# BPS_PowerSupply_v1-0.net
KiCad netlist of a schematic drawn in Altium Designer
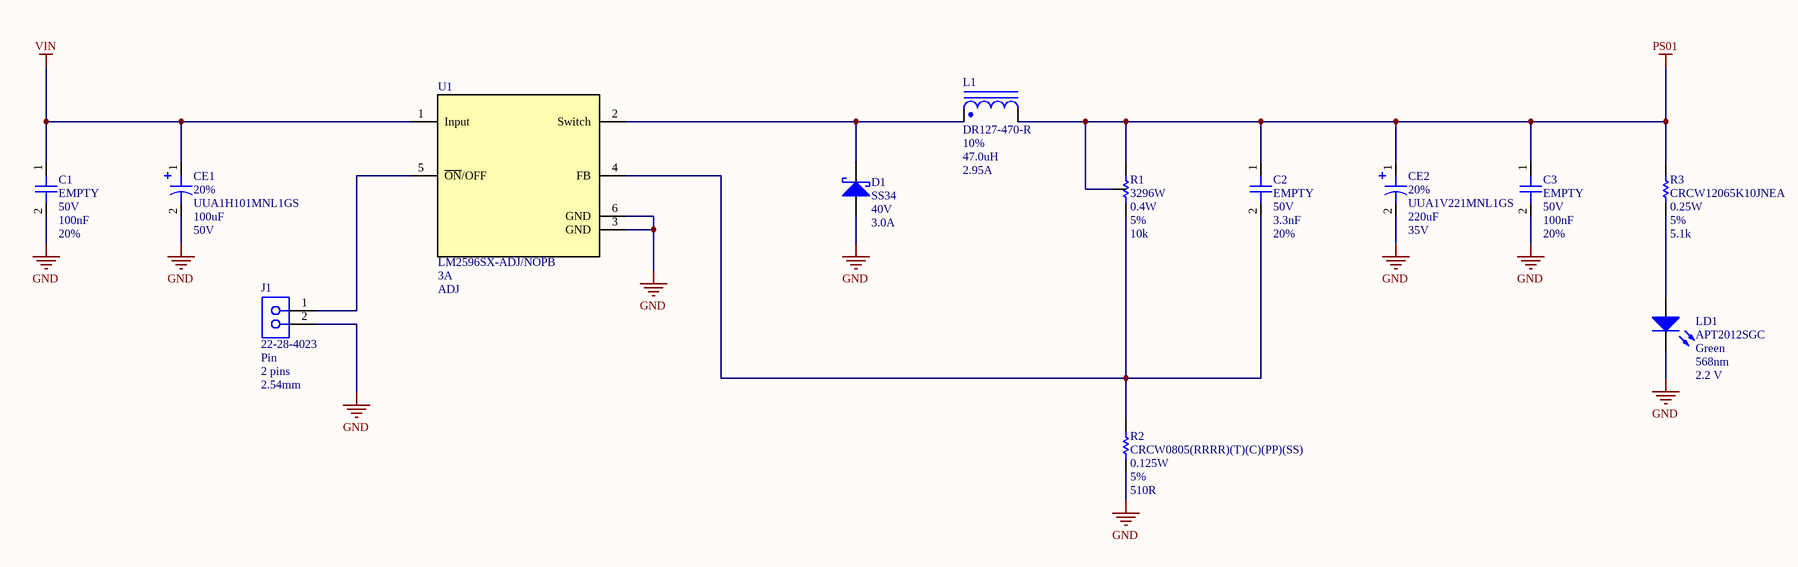
[diagram p0: BPS_PowerSupply_v1-0.SchDoc]

(export (version "E")
  (design (tool "Eeschema 10.0.6"))
  (components
    (comp (ref "C1")
      (value "100nF")
      (footprint "Cap0805")
      (description "Surface Mount Multilayer Ceramic Chip Capacitors  for Commercial Applications")
      (fields
        (field (name "PARTNUMBER1") "EMPTY")
        (field (name "VOLTAGE") "50V")
        (field (name "TOLERANCE") "20%")
        (field (name "Comment") "WCAP-CSGP (0805)")
        (field (name "PUBLISHER") "Lucas Moraes")
      )
      (libsource (lib "CeramicCapacitors") (part "WCAP-CSGP (0805)"))
    )
    (comp (ref "C2")
      (value "3.3nF")
      (footprint "Cap0805")
      (description "Surface Mount Multilayer Ceramic Chip Capacitors  for Commercial Applications")
      (fields
        (field (name "PARTNUMBER1") "EMPTY")
        (field (name "VOLTAGE") "50V")
        (field (name "TOLERANCE") "20%")
        (field (name "Comment") "WCAP-CSGP (0805)")
        (field (name "PUBLISHER") "Lucas Moraes")
      )
      (libsource (lib "CeramicCapacitors") (part "WCAP-CSGP (0805)"))
    )
    (comp (ref "C3")
      (value "100nF")
      (footprint "Cap0805")
      (description "Surface Mount Multilayer Ceramic Chip Capacitors  for Commercial Applications")
      (fields
        (field (name "PARTNUMBER1") "EMPTY")
        (field (name "VOLTAGE") "50V")
        (field (name "TOLERANCE") "20%")
        (field (name "Comment") "WCAP-CSGP (0805)")
        (field (name "PUBLISHER") "Lucas Moraes")
      )
      (libsource (lib "CeramicCapacitors") (part "WCAP-CSGP (0805)"))
    )
    (comp (ref "CE1")
      (value "100uF")
      (footprint "10.0dia(10.0)")
      (description "Electrolytic Capacitor SMD")
      (fields
        (field (name "TOLERANCE") "20%")
        (field (name "PARTNUMBER1") "UUA1H101MNL1GS")
        (field (name "VOLTAGE") "50V")
        (field (name "Comment") "50V 100uF")
        (field (name "PUBLISHER") "Lucas Moraes")
      )
      (libsource (lib "SMDAluminumElectrolyticCapacitorsUUANichicon") (part "50V 100uF"))
    )
    (comp (ref "CE2")
      (value "220uF")
      (footprint "10.0dia(10.0)")
      (description "Electrolytic Capacitor SMD")
      (fields
        (field (name "TOLERANCE") "20%")
        (field (name "PARTNUMBER1") "UUA1V221MNL1GS")
        (field (name "VOLTAGE") "35V")
        (field (name "Comment") "35V 220uF")
        (field (name "PUBLISHER") "Lucas Moraes")
      )
      (libsource (lib "SMDAluminumElectrolyticCapacitorsUUANichicon") (part "35V 220uF"))
    )
    (comp (ref "D1")
      (value "SS34")
      (footprint "DO-214AA")
      (description "Schottky Barrier Rectifiers 40V 3.0A")
      (fields
        (field (name "PARTNUMBER1") "SS34")
        (field (name "VRRM") "40V")
        (field (name "IF") "3.0A")
        (field (name "PUBLISHER") "Lucas Moraes")
      )
      (libsource (lib "SchottkyRectifierDiode") (part "SS34"))
    )
    (comp (ref "J1")
      (value "22-28-4023")
      (footprint "CONSIL02STRMALE_100_100")
      (description "Headers & Wire Housings 02 MODII HDR SRST B/A .100CL")
      (fields
        (field (name "PARTNUMBER1") "22-28-4023")
        (field (name "TYPE") "Pin")
        (field (name "PINS") "2 pins")
        (field (name "PITCH") "2.54mm")
        (field (name "PUBLISHER") "Lucas Moraes")
      )
      (libsource (lib "Header PinSocket") (part "22-28-4023"))
    )
    (comp (ref "L1")
      (value "47.0uH")
      (footprint "DR127")
      (description "High power density, high efficiency, low profile shielded drum core power inductors")
      (fields
        (field (name "PARTNUMBER1") "DR127-470-R")
        (field (name "TOLERANCE") "10%")
        (field (name "CURRENT") "2.95A")
        (field (name "Comment") "DR127")
        (field (name "PUBLISHER") "Lucas Moraes")
      )
      (libsource (lib "Inductor") (part "DR127"))
    )
    (comp (ref "LD1")
      (value "APT2012SGC")
      (footprint "LED0805")
      (description "Standard LEDs - SMD 0805 Green")
      (fields
        (field (name "PARTNUMBER1") "APT2012SGC")
        (field (name "COLOUR") "Green")
        (field (name "WAVELENGTH") "568nm")
        (field (name "VLED") "2.2 V")
        (field (name "PUBLISHER") "Lucas Moraes")
      )
      (libsource (lib "LedDiode") (part "APT2012SGC"))
    )
    (comp (ref "R1")
      (value "10k")
      (footprint "3296W")
      (description "Trimmer Resistors - Through Hole 3/8\" 100Kohms Sealed Vertical Adjust")
      (fields
        (field (name "PARTNUMBER1") "3296W")
        (field (name "POWER") "0.4W")
        (field (name "TOLERANCE") "5%")
        (field (name "Comment") "3296W")
        (field (name "PUBLISHER") "Lucas Moraes")
      )
      (libsource (lib "Potentiometers") (part "3296W"))
    )
    (comp (ref "R2")
      (value "510R")
      (footprint "RES0805")
      (description "Thick Film Chip Resistors with CECC Approval,  available with Established Reliability")
      (fields
        (field (name "PARTNUMBER1") "CRCW0805(RRRR)(T)(C)(PP)(SS)")
        (field (name "POWER") "0.125W")
        (field (name "TOLERANCE") "5%")
        (field (name "Comment") "Chip Resistor")
        (field (name "PUBLISHER") "Lucas Moraes")
      )
      (libsource (lib "ResistorsFixed") (part "CRCW0805"))
    )
    (comp (ref "R3")
      (value "5.1k")
      (footprint "RES1206")
      (description "Thick Film Chip Resistors with CECC Approval,  available with Established Reliability")
      (fields
        (field (name "PARTNUMBER1") "CRCW12065K10JNEA")
        (field (name "POWER") "0.25W")
        (field (name "TOLERANCE") "5%")
        (field (name "Comment") "Chip Resistor")
        (field (name "PUBLISHER") "Lucas Moraes")
      )
      (libsource (lib "ResistorsFixed") (part "CRCW1206"))
    )
    (comp (ref "U1")
      (value "LM2596SX-ADJ/NOPB")
      (footprint "TO-263-5")
      (fields
        (field (name "PARTNUMBER1") "LM2596SX-ADJ/NOPB")
        (field (name "CURRENT") "3A")
        (field (name "VOLTAGE") "ADJ")
        (field (name "PUBLISHER") "Lucas Moraes")
      )
      (libsource (lib "Voltage Regulators") (part "LM2596SX-ADJ/NOPB"))
    )
  )
  (nets
    (net (code "1") (name "GND") (class "Default")
      (node (ref "C1") (pin "2") (pinfunction "2_2") (pintype "passive"))
      (node (ref "C3") (pin "2") (pinfunction "2_2") (pintype "passive"))
      (node (ref "CE1") (pin "2") (pinfunction "2_2") (pintype "passive"))
      (node (ref "CE2") (pin "2") (pinfunction "2_2") (pintype "passive"))
      (node (ref "D1") (pin "A") (pinfunction "A_A") (pintype "passive"))
      (node (ref "J1") (pin "2") (pinfunction "2_2") (pintype "passive"))
      (node (ref "LD1") (pin "K") (pinfunction "K_K") (pintype "passive"))
      (node (ref "R2") (pin "1") (pinfunction "1_1") (pintype "passive"))
      (node (ref "U1") (pin "3") (pinfunction "GND_3") (pintype "passive"))
      (node (ref "U1") (pin "6") (pinfunction "GND_6") (pintype "passive"))
    )
    (net (code "2") (name "Net-(LD1-PadA)") (class "Default")
      (node (ref "LD1") (pin "A") (pinfunction "A_A") (pintype "passive"))
      (node (ref "R3") (pin "1") (pinfunction "1_1") (pintype "passive"))
    )
    (net (code "3") (name "Net-(U1-FB)") (class "Default")
      (node (ref "C2") (pin "2") (pinfunction "2_2") (pintype "passive"))
      (node (ref "R1") (pin "1") (pinfunction "1_1") (pintype "passive"))
      (node (ref "R2") (pin "2") (pinfunction "2_2") (pintype "passive"))
      (node (ref "U1") (pin "4") (pinfunction "FB_4") (pintype "passive"))
    )
    (net (code "4") (name "Net-(U1-Switch)") (class "Default")
      (node (ref "D1") (pin "K") (pinfunction "K_K") (pintype "passive"))
      (node (ref "L1") (pin "1") (pinfunction "1_1") (pintype "passive"))
      (node (ref "U1") (pin "2") (pinfunction "Switch_2") (pintype "passive"))
    )
    (net (code "5") (name "Net-(U1-~{ON}{slash}OFF)") (class "Default")
      (node (ref "J1") (pin "1") (pinfunction "1_1") (pintype "passive"))
      (node (ref "U1") (pin "5") (pinfunction "~{ON}/OFF_5") (pintype "passive"))
    )
    (net (code "6") (name "PS01") (class "Default")
      (node (ref "C2") (pin "1") (pinfunction "1_1") (pintype "passive"))
      (node (ref "C3") (pin "1") (pinfunction "1_1") (pintype "passive"))
      (node (ref "CE2") (pin "1") (pinfunction "1_1") (pintype "passive"))
      (node (ref "L1") (pin "2") (pinfunction "2_2") (pintype "passive"))
      (node (ref "R1") (pin "2") (pinfunction "2_2") (pintype "passive"))
      (node (ref "R1") (pin "3") (pinfunction "3_3") (pintype "passive"))
      (node (ref "R3") (pin "2") (pinfunction "2_2") (pintype "passive"))
    )
    (net (code "7") (name "VIN") (class "Default")
      (node (ref "C1") (pin "1") (pinfunction "1_1") (pintype "passive"))
      (node (ref "CE1") (pin "1") (pinfunction "1_1") (pintype "passive"))
      (node (ref "U1") (pin "1") (pinfunction "Input_1") (pintype "passive"))
    )
  )
)
